# TurnoutModule.net
KiCad netlist of a schematic drawn in EAGLE
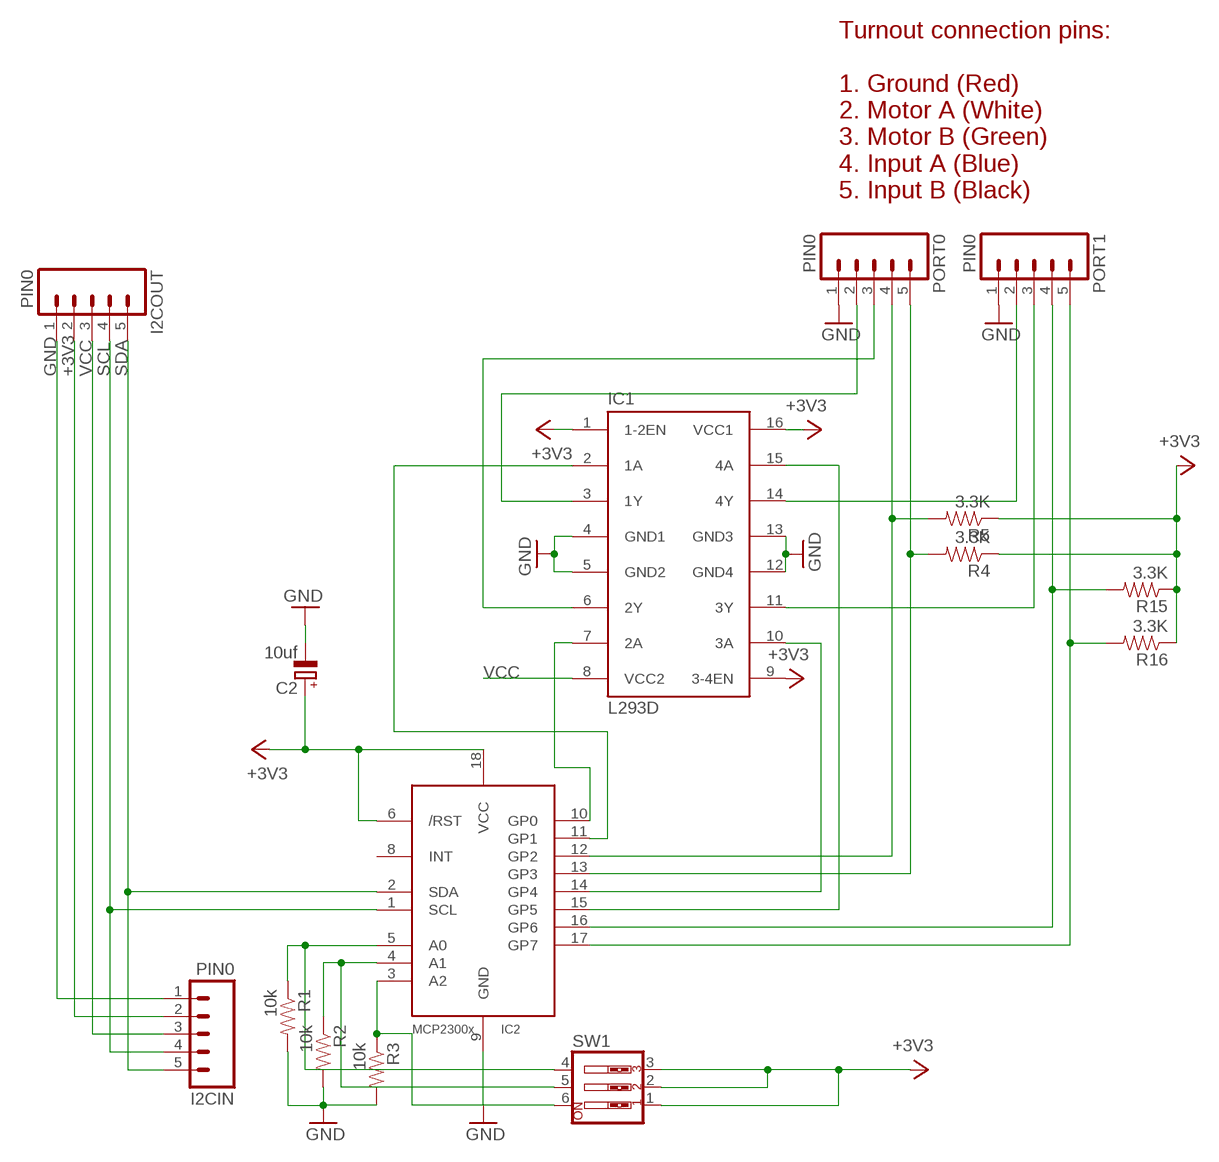
[diagram p0: schematic, sheet 1]

(export (version "E")
  (design (tool "Eeschema 10.0.6"))
  (components
    (comp (ref "C2")
      (value "10uf")
      (footprint "eagle-import:E2,5-6")
      (libsource (lib "eagle-import") (part "CPOL-EUE2.5-6"))
    )
    (comp (ref "I2CIN")
      (value "PIN0")
      (footprint "eagle-import:05P")
      (libsource (lib "eagle-import") (part "M05"))
    )
    (comp (ref "I2COUT")
      (value "PIN0")
      (footprint "eagle-import:05P")
      (libsource (lib "eagle-import") (part "M05"))
    )
    (comp (ref "IC1")
      (value "L293D")
      (footprint "eagle-import:DIL16")
      (libsource (lib "eagle-import") (part "L293D"))
    )
    (comp (ref "IC2")
      (value "MCP23008/P")
      (footprint "eagle-import:DIL18")
      (libsource (lib "eagle-import") (part "MCP23008/P"))
    )
    (comp (ref "PORT0")
      (value "PIN0")
      (footprint "eagle-import:05P")
      (libsource (lib "eagle-import") (part "M05"))
    )
    (comp (ref "PORT1")
      (value "PIN0")
      (footprint "eagle-import:05P")
      (libsource (lib "eagle-import") (part "M05"))
    )
    (comp (ref "R1")
      (value "10k")
      (footprint "eagle-import:AXIAL-0.4")
      (libsource (lib "eagle-import") (part "RESISTORPTH-1/4W"))
    )
    (comp (ref "R2")
      (value "10k")
      (footprint "eagle-import:AXIAL-0.4")
      (libsource (lib "eagle-import") (part "RESISTORPTH-1/4W"))
    )
    (comp (ref "R3")
      (value "10k")
      (footprint "eagle-import:AXIAL-0.4")
      (libsource (lib "eagle-import") (part "RESISTORPTH-1/4W"))
    )
    (comp (ref "R4")
      (value "3.3K")
      (footprint "eagle-import:AXIAL-0.4")
      (libsource (lib "eagle-import") (part "RESISTORPTH-1/4W"))
    )
    (comp (ref "R5")
      (value "3.3K")
      (footprint "eagle-import:AXIAL-0.4")
      (libsource (lib "eagle-import") (part "RESISTORPTH-1/4W"))
    )
    (comp (ref "R15")
      (value "3.3K")
      (footprint "eagle-import:AXIAL-0.4")
      (libsource (lib "eagle-import") (part "RESISTORPTH-1/4W"))
    )
    (comp (ref "R16")
      (value "3.3K")
      (footprint "eagle-import:AXIAL-0.4")
      (libsource (lib "eagle-import") (part "RESISTORPTH-1/4W"))
    )
    (comp (ref "SW1")
      (value "SW_DIP-3")
      (footprint "eagle-import:EDG-03")
      (libsource (lib "eagle-import") (part "SW_DIP-3"))
    )
  )
  (nets
    (net (code "1") (name "+3V3") (class "Default")
      (node (ref "C2") (pin "+") (pinfunction "+_+") (pintype "passive"))
      (node (ref "I2CIN") (pin "2") (pinfunction "2_2") (pintype "passive"))
      (node (ref "I2COUT") (pin "2") (pinfunction "2_2") (pintype "passive"))
      (node (ref "IC1") (pin "1") (pinfunction "1-2EN_1") (pintype "input"))
      (node (ref "IC1") (pin "16") (pinfunction "VCC1_16") (pintype "power_in"))
      (node (ref "IC1") (pin "9") (pinfunction "3-4EN_9") (pintype "input"))
      (node (ref "IC2") (pin "18") (pinfunction "VCC_18") (pintype "power_in"))
      (node (ref "IC2") (pin "6") (pinfunction "/RST_6") (pintype "input"))
      (node (ref "R15") (pin "P$1") (pinfunction "1_P$1") (pintype "passive"))
      (node (ref "R16") (pin "P$1") (pinfunction "1_P$1") (pintype "passive"))
      (node (ref "R4") (pin "P$1") (pinfunction "1_P$1") (pintype "passive"))
      (node (ref "R5") (pin "P$1") (pinfunction "1_P$1") (pintype "passive"))
      (node (ref "SW1") (pin "1") (pinfunction "1_1") (pintype "passive"))
      (node (ref "SW1") (pin "2") (pinfunction "2_2") (pintype "passive"))
      (node (ref "SW1") (pin "3") (pinfunction "3_3") (pintype "passive"))
    )
    (net (code "2") (name "/SCL") (class "Default")
      (node (ref "I2CIN") (pin "4") (pinfunction "4_4") (pintype "passive"))
      (node (ref "I2COUT") (pin "4") (pinfunction "4_4") (pintype "passive"))
      (node (ref "IC2") (pin "1") (pinfunction "SCL_1") (pintype "bidirectional"))
    )
    (net (code "3") (name "/SDA") (class "Default")
      (node (ref "I2CIN") (pin "5") (pinfunction "5_5") (pintype "passive"))
      (node (ref "I2COUT") (pin "5") (pinfunction "5_5") (pintype "passive"))
      (node (ref "IC2") (pin "2") (pinfunction "SDA_2") (pintype "bidirectional"))
    )
    (net (code "4") (name "/VCC") (class "Default")
      (node (ref "I2CIN") (pin "3") (pinfunction "3_3") (pintype "passive"))
      (node (ref "I2COUT") (pin "3") (pinfunction "3_3") (pintype "passive"))
      (node (ref "IC1") (pin "8") (pinfunction "VCC2_8") (pintype "power_in"))
    )
    (net (code "5") (name "GND") (class "Default")
      (node (ref "C2") (pin "-") (pinfunction "-_-") (pintype "passive"))
      (node (ref "I2CIN") (pin "1") (pinfunction "1_1") (pintype "passive"))
      (node (ref "I2COUT") (pin "1") (pinfunction "1_1") (pintype "passive"))
      (node (ref "IC1") (pin "12") (pinfunction "GND4_12") (pintype "power_in"))
      (node (ref "IC1") (pin "13") (pinfunction "GND3_13") (pintype "power_in"))
      (node (ref "IC1") (pin "4") (pinfunction "GND1_4") (pintype "power_in"))
      (node (ref "IC1") (pin "5") (pinfunction "GND2_5") (pintype "power_in"))
      (node (ref "IC2") (pin "9") (pinfunction "GND_9") (pintype "power_in"))
      (node (ref "PORT0") (pin "1") (pinfunction "1_1") (pintype "passive"))
      (node (ref "PORT1") (pin "1") (pinfunction "1_1") (pintype "passive"))
      (node (ref "R1") (pin "P$2") (pinfunction "2_P$2") (pintype "passive"))
      (node (ref "R2") (pin "P$2") (pinfunction "2_P$2") (pintype "passive"))
      (node (ref "R3") (pin "P$2") (pinfunction "2_P$2") (pintype "passive"))
    )
    (net (code "6") (name "Net-(IC1-1A)") (class "Default")
      (node (ref "IC1") (pin "2") (pinfunction "1A_2") (pintype "input"))
      (node (ref "IC2") (pin "11") (pinfunction "GP1_11") (pintype "bidirectional"))
    )
    (net (code "7") (name "Net-(IC1-1Y)") (class "Default")
      (node (ref "IC1") (pin "3") (pinfunction "1Y_3") (pintype "output"))
      (node (ref "PORT0") (pin "2") (pinfunction "2_2") (pintype "passive"))
    )
    (net (code "8") (name "Net-(IC1-2A)") (class "Default")
      (node (ref "IC1") (pin "7") (pinfunction "2A_7") (pintype "input"))
      (node (ref "IC2") (pin "10") (pinfunction "GP0_10") (pintype "bidirectional"))
    )
    (net (code "9") (name "Net-(IC1-2Y)") (class "Default")
      (node (ref "IC1") (pin "6") (pinfunction "2Y_6") (pintype "output"))
      (node (ref "PORT0") (pin "3") (pinfunction "3_3") (pintype "passive"))
    )
    (net (code "10") (name "Net-(IC1-3A)") (class "Default")
      (node (ref "IC1") (pin "10") (pinfunction "3A_10") (pintype "input"))
      (node (ref "IC2") (pin "14") (pinfunction "GP4_14") (pintype "bidirectional"))
    )
    (net (code "11") (name "Net-(IC1-3Y)") (class "Default")
      (node (ref "IC1") (pin "11") (pinfunction "3Y_11") (pintype "output"))
      (node (ref "PORT1") (pin "3") (pinfunction "3_3") (pintype "passive"))
    )
    (net (code "12") (name "Net-(IC1-4A)") (class "Default")
      (node (ref "IC1") (pin "15") (pinfunction "4A_15") (pintype "input"))
      (node (ref "IC2") (pin "15") (pinfunction "GP5_15") (pintype "bidirectional"))
    )
    (net (code "13") (name "Net-(IC1-4Y)") (class "Default")
      (node (ref "IC1") (pin "14") (pinfunction "4Y_14") (pintype "output"))
      (node (ref "PORT1") (pin "2") (pinfunction "2_2") (pintype "passive"))
    )
    (net (code "14") (name "Net-(IC2-A0)") (class "Default")
      (node (ref "IC2") (pin "5") (pinfunction "A0_5") (pintype "input"))
      (node (ref "R1") (pin "P$1") (pinfunction "1_P$1") (pintype "passive"))
      (node (ref "SW1") (pin "4") (pinfunction "4_4") (pintype "passive"))
    )
    (net (code "15") (name "Net-(IC2-A1)") (class "Default")
      (node (ref "IC2") (pin "4") (pinfunction "A1_4") (pintype "input"))
      (node (ref "R2") (pin "P$1") (pinfunction "1_P$1") (pintype "passive"))
      (node (ref "SW1") (pin "5") (pinfunction "5_5") (pintype "passive"))
    )
    (net (code "16") (name "Net-(IC2-A2)") (class "Default")
      (node (ref "IC2") (pin "3") (pinfunction "A2_3") (pintype "input"))
      (node (ref "R3") (pin "P$1") (pinfunction "1_P$1") (pintype "passive"))
      (node (ref "SW1") (pin "6") (pinfunction "6_6") (pintype "passive"))
    )
    (net (code "17") (name "Net-(IC2-GP2)") (class "Default")
      (node (ref "IC2") (pin "12") (pinfunction "GP2_12") (pintype "bidirectional"))
      (node (ref "PORT0") (pin "4") (pinfunction "4_4") (pintype "passive"))
      (node (ref "R5") (pin "P$2") (pinfunction "2_P$2") (pintype "passive"))
    )
    (net (code "18") (name "Net-(IC2-GP3)") (class "Default")
      (node (ref "IC2") (pin "13") (pinfunction "GP3_13") (pintype "bidirectional"))
      (node (ref "PORT0") (pin "5") (pinfunction "5_5") (pintype "passive"))
      (node (ref "R4") (pin "P$2") (pinfunction "2_P$2") (pintype "passive"))
    )
    (net (code "19") (name "Net-(IC2-GP6)") (class "Default")
      (node (ref "IC2") (pin "16") (pinfunction "GP6_16") (pintype "bidirectional"))
      (node (ref "PORT1") (pin "4") (pinfunction "4_4") (pintype "passive"))
      (node (ref "R15") (pin "P$2") (pinfunction "2_P$2") (pintype "passive"))
    )
    (net (code "20") (name "Net-(IC2-GP7)") (class "Default")
      (node (ref "IC2") (pin "17") (pinfunction "GP7_17") (pintype "bidirectional"))
      (node (ref "PORT1") (pin "5") (pinfunction "5_5") (pintype "passive"))
      (node (ref "R16") (pin "P$2") (pinfunction "2_P$2") (pintype "passive"))
    )
    (net (code "21") (name "unconnected-(IC2-INT-Pad8)") (class "Default")
      (node (ref "IC2") (pin "8") (pinfunction "INT_8") (pintype "output"))
    )
  )
)
